# SecurityHost_v1_0.net
KiCad netlist of a schematic drawn in Altium Designer
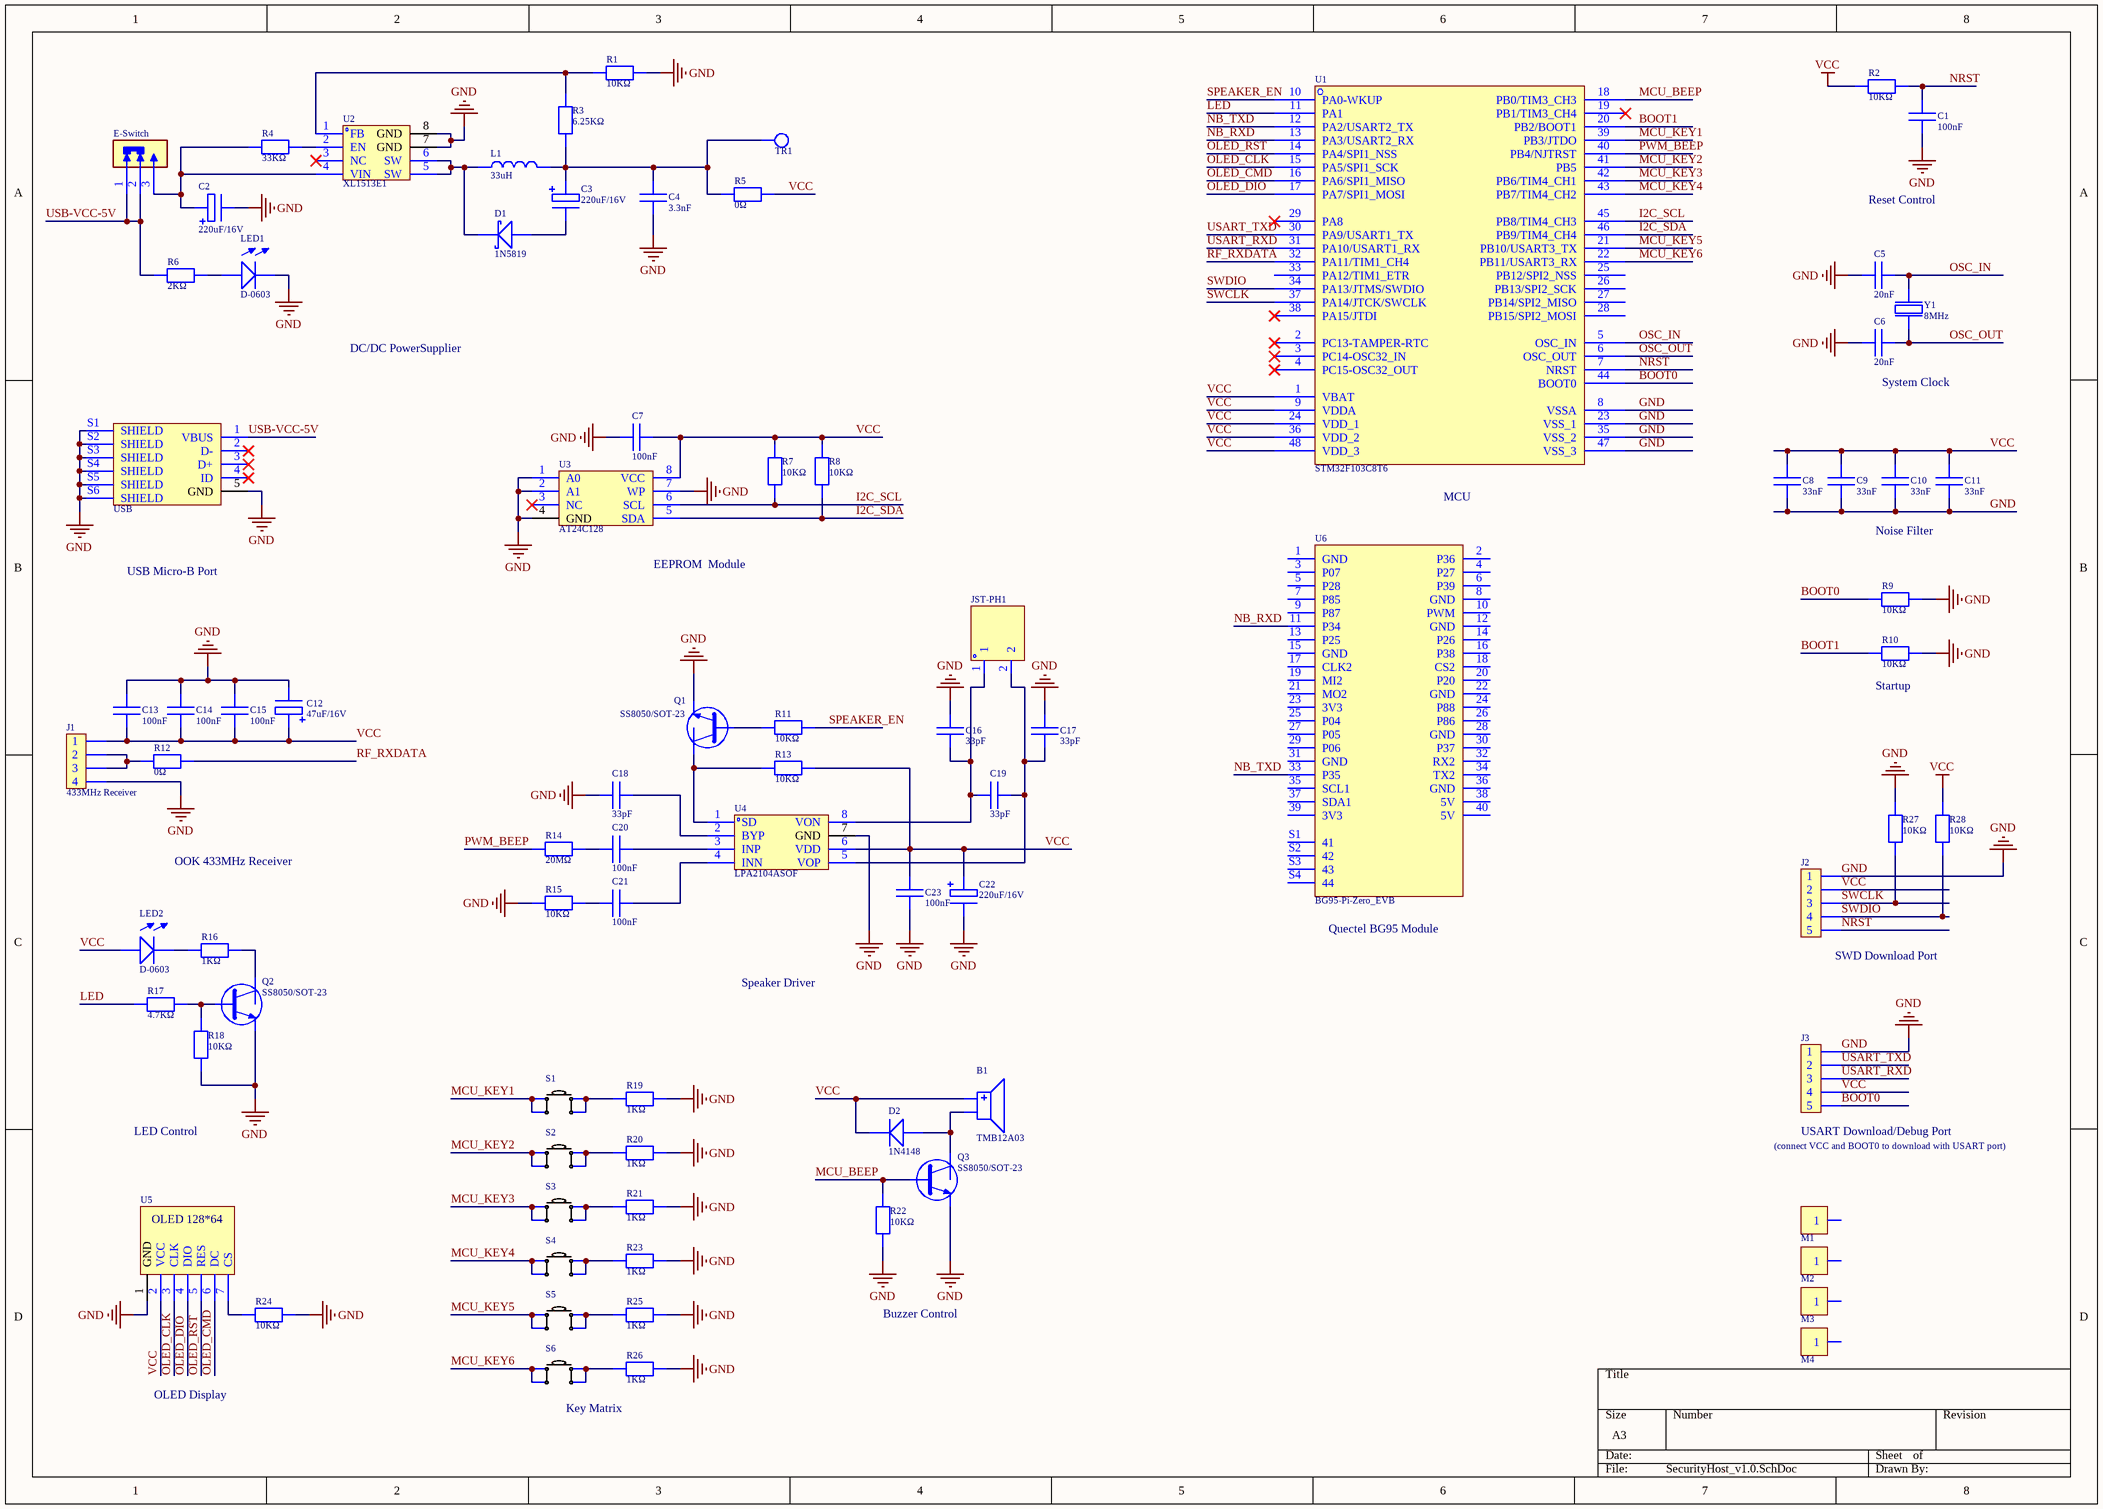
[diagram p0: SecurityHost_v1.0.SchDoc]

(export (version "E")
  (design (tool "Eeschema 10.0.6"))
  (components
    (comp (ref "B1")
      (value "TMB12A03")
      (footprint "Buzzer_TH_BD12.0")
      (libsource (lib "Schematic Library_General") (part "Buzzer_TMB12A03"))
    )
    (comp (ref "C1")
      (value "100nF")
      (footprint "C0603")
      (libsource (lib "Schematic Library_General") (part "Capacitor_0603"))
    )
    (comp (ref "C2")
      (value "220uF/16V")
      (footprint "C(Electrolytic)_SMD-D6.3mm_L7.7mm")
      (libsource (lib "Schematic Library_General") (part "Capacitor_Electrolytic-SMD"))
    )
    (comp (ref "C3")
      (value "220uF/16V")
      (footprint "C(Electrolytic)_SMD-D6.3mm_L7.7mm")
      (libsource (lib "Schematic Library_General") (part "Capacitor_Electrolytic-SMD"))
    )
    (comp (ref "C4")
      (value "3.3nF")
      (footprint "C0603")
      (libsource (lib "Schematic Library_General") (part "Capacitor_0603"))
    )
    (comp (ref "C5")
      (value "20nF")
      (footprint "C0603")
      (libsource (lib "Schematic Library_General") (part "Capacitor_0603"))
    )
    (comp (ref "C6")
      (value "20nF")
      (footprint "C0603")
      (libsource (lib "Schematic Library_General") (part "Capacitor_0603"))
    )
    (comp (ref "C7")
      (value "100nF")
      (footprint "C0603")
      (libsource (lib "Schematic Library_General") (part "Capacitor_0603"))
    )
    (comp (ref "C8")
      (value "33nF")
      (footprint "C0603")
      (libsource (lib "Schematic Library_General") (part "Capacitor_0603"))
    )
    (comp (ref "C9")
      (value "33nF")
      (footprint "C0603")
      (libsource (lib "Schematic Library_General") (part "Capacitor_0603"))
    )
    (comp (ref "C10")
      (value "33nF")
      (footprint "C0603")
      (libsource (lib "Schematic Library_General") (part "Capacitor_0603"))
    )
    (comp (ref "C11")
      (value "33nF")
      (footprint "C0603")
      (libsource (lib "Schematic Library_General") (part "Capacitor_0603"))
    )
    (comp (ref "C12")
      (value "47uF/16V")
      (footprint "C(Electrolytic)_SMD-D6.3mm_L7.7mm")
      (libsource (lib "Schematic Library_General") (part "Capacitor_Electrolytic-SMD"))
    )
    (comp (ref "C13")
      (value "100nF")
      (footprint "C0603")
      (libsource (lib "Schematic Library_General") (part "Capacitor_0603"))
    )
    (comp (ref "C14")
      (value "100nF")
      (footprint "C0603")
      (libsource (lib "Schematic Library_General") (part "Capacitor_0603"))
    )
    (comp (ref "C15")
      (value "100nF")
      (footprint "C0603")
      (libsource (lib "Schematic Library_General") (part "Capacitor_0603"))
    )
    (comp (ref "C16")
      (value "33pF")
      (footprint "C0603")
      (libsource (lib "Schematic Library_General") (part "Capacitor_0603"))
    )
    (comp (ref "C17")
      (value "33pF")
      (footprint "C0603")
      (libsource (lib "Schematic Library_General") (part "Capacitor_0603"))
    )
    (comp (ref "C18")
      (value "33pF")
      (footprint "C0603")
      (libsource (lib "Schematic Library_General") (part "Capacitor_0603"))
    )
    (comp (ref "C19")
      (value "33pF")
      (footprint "C0603")
      (libsource (lib "Schematic Library_General") (part "Capacitor_0603"))
    )
    (comp (ref "C20")
      (value "100nF")
      (footprint "C0603")
      (libsource (lib "Schematic Library_General") (part "Capacitor_0603"))
    )
    (comp (ref "C21")
      (value "100nF")
      (footprint "C0603")
      (libsource (lib "Schematic Library_General") (part "Capacitor_0603"))
    )
    (comp (ref "C22")
      (value "220uF/16V")
      (footprint "C(Electrolytic)_SMD-D6.3mm_L7.7mm")
      (libsource (lib "Schematic Library_General") (part "Capacitor_Electrolytic-SMD"))
    )
    (comp (ref "C23")
      (value "100nF")
      (footprint "C0603")
      (libsource (lib "Schematic Library_General") (part "Capacitor_0603"))
    )
    (comp (ref "D1")
      (value "1N5819")
      (footprint "SOD-123F")
      (libsource (lib "Schematic Library_General") (part "Schottky Diodes_SOD123F"))
    )
    (comp (ref "D2")
      (value "1N4148")
      (footprint "SOD-123")
      (libsource (lib "Schematic Library_General") (part "Diode-FastSwitching_SOD123"))
    )
    (comp (ref "E-Switch")
      (value "E-Switch_3Pin-Slide")
      (footprint "E-Switch_3Pin-Slide")
      (libsource (lib "Schematic Library_General") (part "E-Switch_3Pin-Slide"))
    )
    (comp (ref "J1")
      (value "433MHz Receiver")
      (footprint "PinSocket_4Pin-2.54mm")
      (description "Straight Single Row, Square Pitch, 2.54mm")
      (libsource (lib "Schematic Library_General") (part "PinSocket_4Pin"))
    )
    (comp (ref "J2")
      (value "SWD Download Port")
      (footprint "PinHeader_5Pin-2.54mm")
      (description "Straight Single Row, Square Pitch, 2.54mm")
      (libsource (lib "Schematic Library_General") (part "PinHeader_5Pin"))
    )
    (comp (ref "J3")
      (value "PinHeader_5Pin")
      (footprint "PinHeader_5Pin-2.54mm")
      (description "Straight Single Row, Square Pitch, 2.54mm")
      (libsource (lib "Schematic Library_General") (part "PinHeader_5Pin"))
    )
    (comp (ref "JST-PH1")
      (value "JST-PH2.0_2Pin-TH-Vertical")
      (footprint "Connector-JST-PH2.0-2Pin_TH-Vertical")
      (libsource (lib "Schematic Library_General") (part "JST-PH2.0_2Pin-TH-Vertical"))
    )
    (comp (ref "L1")
      (value "33uH")
      (footprint "L1040-Integrated Molded")
      (libsource (lib "Schematic Library_General") (part "Inductor_Integrated Molded_1040"))
    )
    (comp (ref "LED1")
      (value "D-0603")
      (footprint "LED0603-Castellated")
      (libsource (lib "Schematic Library_General") (part "LED_0603"))
    )
    (comp (ref "LED2")
      (value "D-0603")
      (footprint "LED0603-Castellated")
      (libsource (lib "Schematic Library_General") (part "LED_0603"))
    )
    (comp (ref "M1")
      (value "PCB Mounting Hole")
      (footprint "PCB Mounting Hole")
      (description "Mounting Hole")
      (libsource (lib "Schematic Library_General") (part "PCB Mounting Hole"))
    )
    (comp (ref "M2")
      (value "PCB Mounting Hole")
      (footprint "PCB Mounting Hole")
      (description "Mounting Hole")
      (libsource (lib "Schematic Library_General") (part "PCB Mounting Hole"))
    )
    (comp (ref "M3")
      (value "PCB Mounting Hole")
      (footprint "PCB Mounting Hole")
      (description "Mounting Hole")
      (libsource (lib "Schematic Library_General") (part "PCB Mounting Hole"))
    )
    (comp (ref "M4")
      (value "PCB Mounting Hole")
      (footprint "PCB Mounting Hole")
      (description "Mounting Hole")
      (libsource (lib "Schematic Library_General") (part "PCB Mounting Hole"))
    )
    (comp (ref "Q1")
      (value "SS8050/SOT-23")
      (footprint "SOT-23-3")
      (libsource (lib "") (part "NPN_SOT-23-3_1"))
    )
    (comp (ref "Q2")
      (value "SS8050/SOT-23")
      (footprint "SOT-23-3")
      (libsource (lib "Schematic Library_General") (part "NPN_SOT-23-3"))
    )
    (comp (ref "Q3")
      (value "SS8050/SOT-23")
      (footprint "SOT-23-3")
      (libsource (lib "Schematic Library_General") (part "NPN_SOT-23-3"))
    )
    (comp (ref "R1")
      (value "10KΩ")
      (footprint "R0805")
      (libsource (lib "Schematic Library_General") (part "Resistor_0805"))
    )
    (comp (ref "R2")
      (value "10KΩ")
      (footprint "R0603")
      (libsource (lib "Schematic Library_General") (part "Resistor_0603"))
    )
    (comp (ref "R3") (value "6.25KΩ") (footprint "R0805") (libsource (lib "") (part "Resistor_0805_1")))
    (comp (ref "R4")
      (value "33KΩ")
      (footprint "R0603")
      (libsource (lib "Schematic Library_General") (part "Resistor_0603"))
    )
    (comp (ref "R5")
      (value "0Ω")
      (footprint "R0805")
      (libsource (lib "Schematic Library_General") (part "Resistor_0805"))
    )
    (comp (ref "R6")
      (value "2KΩ")
      (footprint "R0805")
      (libsource (lib "Schematic Library_General") (part "Resistor_0805"))
    )
    (comp (ref "R7") (value "10KΩ") (footprint "R0603") (libsource (lib "") (part "Resistor_0603_2")))
    (comp (ref "R8") (value "10KΩ") (footprint "R0603") (libsource (lib "") (part "Resistor_0603_2")))
    (comp (ref "R9")
      (value "10KΩ")
      (footprint "R0603")
      (libsource (lib "Schematic Library_General") (part "Resistor_0603"))
    )
    (comp (ref "R10")
      (value "10KΩ")
      (footprint "R0603")
      (libsource (lib "Schematic Library_General") (part "Resistor_0603"))
    )
    (comp (ref "R11") (value "10KΩ") (footprint "R0603") (libsource (lib "") (part "Resistor_0603_1")))
    (comp (ref "R12")
      (value "0Ω")
      (footprint "R0805")
      (libsource (lib "Schematic Library_General") (part "Resistor_0805"))
    )
    (comp (ref "R13")
      (value "10KΩ")
      (footprint "R0603")
      (libsource (lib "Schematic Library_General") (part "Resistor_0603"))
    )
    (comp (ref "R14")
      (value "20MΩ")
      (footprint "R0603")
      (libsource (lib "Schematic Library_General") (part "Resistor_0603"))
    )
    (comp (ref "R15")
      (value "10KΩ")
      (footprint "R0603")
      (libsource (lib "Schematic Library_General") (part "Resistor_0603"))
    )
    (comp (ref "R16")
      (value "1KΩ")
      (footprint "R0603")
      (libsource (lib "Schematic Library_General") (part "Resistor_0603"))
    )
    (comp (ref "R17")
      (value "4.7KΩ")
      (footprint "R0603")
      (libsource (lib "Schematic Library_General") (part "Resistor_0603"))
    )
    (comp (ref "R18") (value "10KΩ") (footprint "R0603") (libsource (lib "") (part "Resistor_0603_2")))
    (comp (ref "R19")
      (value "1KΩ")
      (footprint "R0603")
      (libsource (lib "Schematic Library_General") (part "Resistor_0603"))
    )
    (comp (ref "R20")
      (value "1KΩ")
      (footprint "R0603")
      (libsource (lib "Schematic Library_General") (part "Resistor_0603"))
    )
    (comp (ref "R21")
      (value "1KΩ")
      (footprint "R0603")
      (libsource (lib "Schematic Library_General") (part "Resistor_0603"))
    )
    (comp (ref "R22") (value "10KΩ") (footprint "R0603") (libsource (lib "") (part "Resistor_0603_2")))
    (comp (ref "R23")
      (value "1KΩ")
      (footprint "R0603")
      (libsource (lib "Schematic Library_General") (part "Resistor_0603"))
    )
    (comp (ref "R24")
      (value "10KΩ")
      (footprint "R0603")
      (libsource (lib "Schematic Library_General") (part "Resistor_0603"))
    )
    (comp (ref "R25")
      (value "1KΩ")
      (footprint "R0603")
      (libsource (lib "Schematic Library_General") (part "Resistor_0603"))
    )
    (comp (ref "R26")
      (value "1KΩ")
      (footprint "R0603")
      (libsource (lib "Schematic Library_General") (part "Resistor_0603"))
    )
    (comp (ref "R27") (value "10KΩ") (footprint "R0603") (libsource (lib "") (part "Resistor_0603_2")))
    (comp (ref "R28") (value "10KΩ") (footprint "R0603") (libsource (lib "") (part "Resistor_0603_2")))
    (comp (ref "S1")
      (value "Button_Push_4Pin_TH")
      (footprint "Tactile Switch_TH_SPST-L6.0-W6.0")
      (libsource (lib "Schematic Library_General") (part "Button_Push_4Pin_TH"))
    )
    (comp (ref "S2")
      (value "Button_Push_4Pin_TH")
      (footprint "Tactile Switch_TH_SPST-L6.0-W6.0")
      (libsource (lib "Schematic Library_General") (part "Button_Push_4Pin_TH"))
    )
    (comp (ref "S3")
      (value "Button_Push_4Pin_TH")
      (footprint "Tactile Switch_TH_SPST-L6.0-W6.0")
      (libsource (lib "Schematic Library_General") (part "Button_Push_4Pin_TH"))
    )
    (comp (ref "S4")
      (value "Button_Push_4Pin_TH")
      (footprint "Tactile Switch_TH_SPST-L6.0-W6.0")
      (libsource (lib "Schematic Library_General") (part "Button_Push_4Pin_TH"))
    )
    (comp (ref "S5")
      (value "Button_Push_4Pin_TH")
      (footprint "Tactile Switch_TH_SPST-L6.0-W6.0")
      (libsource (lib "Schematic Library_General") (part "Button_Push_4Pin_TH"))
    )
    (comp (ref "S6")
      (value "Button_Push_4Pin_TH")
      (footprint "Tactile Switch_TH_SPST-L6.0-W6.0")
      (libsource (lib "Schematic Library_General") (part "Button_Push_4Pin_TH"))
    )
    (comp (ref "TR1")
      (value "Test Ring")
      (footprint "Test Ring_TH-BD2.54mm")
      (libsource (lib "Schematic Library_General") (part "Test Ring"))
    )
    (comp (ref "U1")
      (value "STM32F103C8T6")
      (footprint "LQFP_48Pin_L7.0-W7.0-P0.5")
      (libsource (lib "Schematic Library_General") (part "STM32_LQFP-48Pin-7x7mm"))
    )
    (comp (ref "U2")
      (value "XL1513E1")
      (footprint "SOIC_8Pin-L5.0-W4.0")
      (description "3.6V to 18V Input, 0.8V to 16V Output, Step-down type 2A")
      (libsource (lib "Schematic Library_General") (part "DC/DC Converter_XL1513_SOP8"))
    )
    (comp (ref "U3")
      (value "AT24C128")
      (footprint "SOIC_8Pin-L5.0-W4.0")
      (libsource (lib "Schematic Library_General") (part "EEPROM_AT24C128_SOP8"))
    )
    (comp (ref "U4")
      (value "LPA2104ASOF")
      (footprint "SOIC_8Pin-L5.0-W4.0")
      (libsource (lib "Schematic Library_General") (part "Audio Amplifier_SOP8"))
    )
    (comp (ref "U5")
      (value "OLED Display_7Pin")
      (footprint "OLED Display_7Pin")
      (description "0.96'', 128x64")
      (libsource (lib "Schematic Library_General") (part "OLED Display_7Pin"))
    )
    (comp (ref "U6")
      (value "BG95-Pi-Zero_EVB")
      (footprint "Quectel-BG95-Pi-Zero_EVB_PinSocket")
      (description "P34: USART4_RX, P35: USART4_TX")
      (libsource (lib "Schematic Library_General") (part "Quectel-BG95-Pi-Zero_EVB"))
    )
    (comp (ref "USB")
      (value "USB_Micro-B-Molex")
      (footprint "USB_Micro-B")
      (libsource (lib "Schematic Library_General") (part "USB_Micro-B-Molex"))
    )
    (comp (ref "Y1")
      (value "8MHz")
      (footprint "Crystal_TH_HC-49S-L11.5-W4.5")
      (libsource (lib "Schematic Library_General") (part "Crystal_2Pin_TH"))
    )
  )
  (nets
    (net (code "1") (name "/BOOT0") (class "Default")
      (node (ref "J3") (pin "5") (pinfunction "5_5") (pintype "passive"))
      (node (ref "R9") (pin "1") (pintype "passive"))
      (node (ref "U1") (pin "44") (pinfunction "BOOT0_44") (pintype "passive"))
    )
    (net (code "2") (name "/BOOT1") (class "Default")
      (node (ref "R10") (pin "1") (pintype "passive"))
      (node (ref "U1") (pin "20") (pinfunction "PB2/BOOT1_20") (pintype "passive"))
    )
    (net (code "3") (name "/I2C_SCL") (class "Default")
      (node (ref "R7") (pin "1") (pintype "passive"))
      (node (ref "U1") (pin "45") (pinfunction "PB8/TIM4_CH3_45") (pintype "passive"))
      (node (ref "U3") (pin "6") (pinfunction "SCL_6") (pintype "passive"))
    )
    (net (code "4") (name "/I2C_SDA") (class "Default")
      (node (ref "R8") (pin "1") (pintype "passive"))
      (node (ref "U1") (pin "46") (pinfunction "PB9/TIM4_CH4_46") (pintype "passive"))
      (node (ref "U3") (pin "5") (pinfunction "SDA_5") (pintype "passive"))
    )
    (net (code "5") (name "/LED") (class "Default")
      (node (ref "R17") (pin "1") (pintype "passive"))
      (node (ref "U1") (pin "11") (pinfunction "PA1_11") (pintype "passive"))
    )
    (net (code "6") (name "/MCU_BEEP") (class "Default")
      (node (ref "Q3") (pin "1") (pintype "passive"))
      (node (ref "R22") (pin "2") (pintype "passive"))
      (node (ref "U1") (pin "18") (pinfunction "PB0/TIM3_CH3_18") (pintype "passive"))
    )
    (net (code "7") (name "/MCU_KEY1") (class "Default")
      (node (ref "S1") (pin "1") (pinfunction "1_1") (pintype "passive"))
      (node (ref "S1") (pin "2") (pinfunction "2_2") (pintype "passive"))
      (node (ref "U1") (pin "39") (pinfunction "PB3/JTDO_39") (pintype "passive"))
    )
    (net (code "8") (name "/MCU_KEY2") (class "Default")
      (node (ref "S2") (pin "1") (pinfunction "1_1") (pintype "passive"))
      (node (ref "S2") (pin "2") (pinfunction "2_2") (pintype "passive"))
      (node (ref "U1") (pin "41") (pinfunction "PB5_41") (pintype "passive"))
    )
    (net (code "9") (name "/MCU_KEY3") (class "Default")
      (node (ref "S3") (pin "1") (pinfunction "1_1") (pintype "passive"))
      (node (ref "S3") (pin "2") (pinfunction "2_2") (pintype "passive"))
      (node (ref "U1") (pin "42") (pinfunction "PB6/TIM4_CH1_42") (pintype "passive"))
    )
    (net (code "10") (name "/MCU_KEY4") (class "Default")
      (node (ref "S4") (pin "1") (pinfunction "1_1") (pintype "passive"))
      (node (ref "S4") (pin "2") (pinfunction "2_2") (pintype "passive"))
      (node (ref "U1") (pin "43") (pinfunction "PB7/TIM4_CH2_43") (pintype "passive"))
    )
    (net (code "11") (name "/MCU_KEY5") (class "Default")
      (node (ref "S5") (pin "1") (pinfunction "1_1") (pintype "passive"))
      (node (ref "S5") (pin "2") (pinfunction "2_2") (pintype "passive"))
      (node (ref "U1") (pin "21") (pinfunction "PB10/USART3_TX_21") (pintype "passive"))
    )
    (net (code "12") (name "/MCU_KEY6") (class "Default")
      (node (ref "S6") (pin "1") (pinfunction "1_1") (pintype "passive"))
      (node (ref "S6") (pin "2") (pinfunction "2_2") (pintype "passive"))
      (node (ref "U1") (pin "22") (pinfunction "PB11/USART3_RX_22") (pintype "passive"))
    )
    (net (code "13") (name "/NB_RXD") (class "Default")
      (node (ref "U1") (pin "13") (pinfunction "PA3/USART2_RX_13") (pintype "passive"))
      (node (ref "U6") (pin "11") (pinfunction "P34_11") (pintype "passive"))
    )
    (net (code "14") (name "/NB_TXD") (class "Default")
      (node (ref "U1") (pin "12") (pinfunction "PA2/USART2_TX_12") (pintype "passive"))
      (node (ref "U6") (pin "33") (pinfunction "P35_33") (pintype "passive"))
    )
    (net (code "15") (name "/NRST") (class "Default")
      (node (ref "C1") (pin "2") (pintype "passive"))
      (node (ref "J2") (pin "5") (pinfunction "5_5") (pintype "passive"))
      (node (ref "R2") (pin "2") (pintype "passive"))
      (node (ref "U1") (pin "7") (pinfunction "NRST_7") (pintype "passive"))
    )
    (net (code "16") (name "/OLED_CLK") (class "Default")
      (node (ref "U1") (pin "15") (pinfunction "PA5/SPI1_SCK_15") (pintype "passive"))
      (node (ref "U5") (pin "3") (pinfunction "CLK_3") (pintype "passive"))
    )
    (net (code "17") (name "/OLED_CMD") (class "Default")
      (node (ref "U1") (pin "16") (pinfunction "PA6/SPI1_MISO_16") (pintype "passive"))
      (node (ref "U5") (pin "6") (pinfunction "DC_6") (pintype "passive"))
    )
    (net (code "18") (name "/OLED_DIO") (class "Default")
      (node (ref "U1") (pin "17") (pinfunction "PA7/SPI1_MOSI_17") (pintype "passive"))
      (node (ref "U5") (pin "4") (pinfunction "DIO_4") (pintype "passive"))
    )
    (net (code "19") (name "/OLED_RST") (class "Default")
      (node (ref "U1") (pin "14") (pinfunction "PA4/SPI1_NSS_14") (pintype "passive"))
      (node (ref "U5") (pin "5") (pinfunction "RES_5") (pintype "passive"))
    )
    (net (code "20") (name "/OSC_IN") (class "Default")
      (node (ref "C5") (pin "2") (pintype "passive"))
      (node (ref "U1") (pin "5") (pinfunction "OSC_IN_5") (pintype "passive"))
      (node (ref "Y1") (pin "2") (pinfunction "2_2") (pintype "passive"))
    )
    (net (code "21") (name "/OSC_OUT") (class "Default")
      (node (ref "C6") (pin "2") (pintype "passive"))
      (node (ref "U1") (pin "6") (pinfunction "OSC_OUT_6") (pintype "passive"))
      (node (ref "Y1") (pin "1") (pinfunction "1_1") (pintype "passive"))
    )
    (net (code "22") (name "/PWM_BEEP") (class "Default")
      (node (ref "R14") (pin "1") (pintype "passive"))
      (node (ref "U1") (pin "40") (pinfunction "PB4/NJTRST_40") (pintype "passive"))
    )
    (net (code "23") (name "/RF_RXDATA") (class "Default")
      (node (ref "R12") (pin "2") (pintype "passive"))
      (node (ref "U1") (pin "32") (pinfunction "PA11/TIM1_CH4_32") (pintype "passive"))
    )
    (net (code "24") (name "/SPEAKER_EN") (class "Default")
      (node (ref "R11") (pin "1") (pintype "passive"))
      (node (ref "U1") (pin "10") (pinfunction "PA0-WKUP_10") (pintype "passive"))
    )
    (net (code "25") (name "/SWCLK") (class "Default")
      (node (ref "J2") (pin "3") (pinfunction "3_3") (pintype "passive"))
      (node (ref "R27") (pin "1") (pintype "passive"))
      (node (ref "U1") (pin "37") (pinfunction "PA14/JTCK/SWCLK_37") (pintype "passive"))
    )
    (net (code "26") (name "/SWDIO") (class "Default")
      (node (ref "J2") (pin "4") (pinfunction "4_4") (pintype "passive"))
      (node (ref "R28") (pin "1") (pintype "passive"))
      (node (ref "U1") (pin "34") (pinfunction "PA13/JTMS/SWDIO_34") (pintype "passive"))
    )
    (net (code "27") (name "/USART_RXD") (class "Default")
      (node (ref "J3") (pin "3") (pinfunction "3_3") (pintype "passive"))
      (node (ref "U1") (pin "31") (pinfunction "PA10/USART1_RX_31") (pintype "passive"))
    )
    (net (code "28") (name "/USART_TXD") (class "Default")
      (node (ref "J3") (pin "2") (pinfunction "2_2") (pintype "passive"))
      (node (ref "U1") (pin "30") (pinfunction "PA9/USART1_TX_30") (pintype "passive"))
    )
    (net (code "29") (name "/USB-VCC-5V") (class "Default")
      (node (ref "E-Switch") (pin "1") (pinfunction "NC_1") (pintype "passive"))
      (node (ref "E-Switch") (pin "2") (pinfunction "COM_2") (pintype "passive"))
      (node (ref "R6") (pin "1") (pintype "passive"))
      (node (ref "USB") (pin "1") (pinfunction "VBUS_1") (pintype "passive"))
    )
    (net (code "30") (name "GND") (class "Default")
      (node (ref "C1") (pin "1") (pintype "passive"))
      (node (ref "C10") (pin "1") (pintype "passive"))
      (node (ref "C11") (pin "1") (pintype "passive"))
      (node (ref "C12") (pin "2") (pintype "passive"))
      (node (ref "C13") (pin "2") (pintype "passive"))
      (node (ref "C14") (pin "2") (pintype "passive"))
      (node (ref "C15") (pin "2") (pintype "passive"))
      (node (ref "C16") (pin "2") (pintype "passive"))
      (node (ref "C17") (pin "2") (pintype "passive"))
      (node (ref "C18") (pin "2") (pintype "passive"))
      (node (ref "C2") (pin "2") (pintype "passive"))
      (node (ref "C22") (pin "2") (pintype "passive"))
      (node (ref "C23") (pin "2") (pintype "passive"))
      (node (ref "C4") (pin "1") (pintype "passive"))
      (node (ref "C5") (pin "1") (pintype "passive"))
      (node (ref "C6") (pin "1") (pintype "passive"))
      (node (ref "C7") (pin "1") (pintype "passive"))
      (node (ref "C8") (pin "1") (pintype "passive"))
      (node (ref "C9") (pin "1") (pintype "passive"))
      (node (ref "J1") (pin "4") (pinfunction "4_4") (pintype "passive"))
      (node (ref "J2") (pin "1") (pinfunction "1_1") (pintype "passive"))
      (node (ref "J3") (pin "1") (pinfunction "1_1") (pintype "passive"))
      (node (ref "LED1") (pin "2") (pintype "passive"))
      (node (ref "Q1") (pin "2") (pintype "passive"))
      (node (ref "Q2") (pin "2") (pintype "passive"))
      (node (ref "Q3") (pin "2") (pintype "passive"))
      (node (ref "R1") (pin "2") (pintype "passive"))
      (node (ref "R10") (pin "2") (pintype "passive"))
      (node (ref "R15") (pin "1") (pintype "passive"))
      (node (ref "R18") (pin "1") (pintype "passive"))
      (node (ref "R19") (pin "2") (pintype "passive"))
      (node (ref "R20") (pin "2") (pintype "passive"))
      (node (ref "R21") (pin "2") (pintype "passive"))
      (node (ref "R22") (pin "1") (pintype "passive"))
      (node (ref "R23") (pin "2") (pintype "passive"))
      (node (ref "R24") (pin "2") (pintype "passive"))
      (node (ref "R25") (pin "2") (pintype "passive"))
      (node (ref "R26") (pin "2") (pintype "passive"))
      (node (ref "R27") (pin "2") (pintype "passive"))
      (node (ref "R9") (pin "2") (pintype "passive"))
      (node (ref "U1") (pin "23") (pinfunction "VSS_1_23") (pintype "passive"))
      (node (ref "U1") (pin "35") (pinfunction "VSS_2_35") (pintype "passive"))
      (node (ref "U1") (pin "47") (pinfunction "VSS_3_47") (pintype "passive"))
      (node (ref "U1") (pin "8") (pinfunction "VSSA_8") (pintype "passive"))
      (node (ref "U2") (pin "7") (pinfunction "GND_7") (pintype "passive"))
      (node (ref "U2") (pin "8") (pinfunction "GND_8") (pintype "passive"))
      (node (ref "U3") (pin "1") (pinfunction "A0_1") (pintype "passive"))
      (node (ref "U3") (pin "2") (pinfunction "A1_2") (pintype "passive"))
      (node (ref "U3") (pin "4") (pinfunction "GND_4") (pintype "passive"))
      (node (ref "U3") (pin "7") (pinfunction "WP_7") (pintype "passive"))
      (node (ref "U4") (pin "7") (pinfunction "GND_7") (pintype "passive"))
      (node (ref "U5") (pin "1") (pinfunction "GND_1") (pintype "passive"))
      (node (ref "USB") (pin "5") (pinfunction "GND_5") (pintype "passive"))
      (node (ref "USB") (pin "S1") (pinfunction "SHIELD_S1") (pintype "passive"))
      (node (ref "USB") (pin "S2") (pinfunction "SHIELD_S2") (pintype "passive"))
      (node (ref "USB") (pin "S3") (pinfunction "SHIELD_S3") (pintype "passive"))
      (node (ref "USB") (pin "S4") (pinfunction "SHIELD_S4") (pintype "passive"))
      (node (ref "USB") (pin "S5") (pinfunction "SHIELD_S5") (pintype "passive"))
      (node (ref "USB") (pin "S6") (pinfunction "SHIELD_S6") (pintype "passive"))
    )
    (net (code "31") (name "Net-(B1-Pad2)") (class "Default")
      (node (ref "B1") (pin "2") (pintype "passive"))
      (node (ref "D2") (pin "2") (pintype "passive"))
      (node (ref "Q3") (pin "3") (pintype "passive"))
    )
    (net (code "32") (name "Net-(C3-Pad1)") (class "Default")
      (node (ref "C3") (pin "1") (pintype "passive"))
      (node (ref "C4") (pin "2") (pintype "passive"))
      (node (ref "L1") (pin "2") (pintype "passive"))
      (node (ref "R3") (pin "1") (pintype "passive"))
      (node (ref "R5") (pin "1") (pintype "passive"))
      (node (ref "TR1") (pin "1") (pinfunction "1_1") (pintype "passive"))
    )
    (net (code "33") (name "Net-(C3-Pad2)") (class "Default")
      (node (ref "C3") (pin "2") (pintype "passive"))
      (node (ref "D1") (pin "2") (pintype "passive"))
    )
    (net (code "34") (name "Net-(C20-Pad1)") (class "Default")
      (node (ref "C20") (pin "1") (pintype "passive"))
      (node (ref "R14") (pin "2") (pintype "passive"))
    )
    (net (code "35") (name "Net-(C21-Pad1)") (class "Default")
      (node (ref "C21") (pin "1") (pintype "passive"))
      (node (ref "R15") (pin "2") (pintype "passive"))
    )
    (net (code "36") (name "Net-(D1-Pad1)") (class "Default")
      (node (ref "D1") (pin "1") (pintype "passive"))
      (node (ref "L1") (pin "1") (pintype "passive"))
      (node (ref "U2") (pin "5") (pinfunction "SW_5") (pintype "passive"))
      (node (ref "U2") (pin "6") (pinfunction "SW_6") (pintype "passive"))
    )
    (net (code "37") (name "Net-(E-Switch-NO)") (class "Default")
      (node (ref "C2") (pin "1") (pintype "passive"))
      (node (ref "E-Switch") (pin "3") (pinfunction "NO_3") (pintype "passive"))
      (node (ref "R4") (pin "1") (pintype "passive"))
      (node (ref "U2") (pin "4") (pinfunction "VIN_4") (pintype "passive"))
    )
    (net (code "38") (name "Net-(J1-Pad2)") (class "Default")
      (node (ref "J1") (pin "2") (pinfunction "2_2") (pintype "passive"))
      (node (ref "J1") (pin "3") (pinfunction "3_3") (pintype "passive"))
      (node (ref "R12") (pin "1") (pintype "passive"))
    )
    (net (code "39") (name "Net-(LED1-Pad1)") (class "Default")
      (node (ref "LED1") (pin "1") (pintype "passive"))
      (node (ref "R6") (pin "2") (pintype "passive"))
    )
    (net (code "40") (name "Net-(LED2-Pad2)") (class "Default")
      (node (ref "LED2") (pin "2") (pintype "passive"))
      (node (ref "R16") (pin "1") (pintype "passive"))
    )
    (net (code "41") (name "Net-(Q1-Pad1)") (class "Default")
      (node (ref "Q1") (pin "1") (pintype "passive"))
      (node (ref "R11") (pin "2") (pintype "passive"))
    )
    (net (code "42") (name "Net-(Q2-Pad1)") (class "Default")
      (node (ref "Q2") (pin "1") (pintype "passive"))
      (node (ref "R17") (pin "2") (pintype "passive"))
      (node (ref "R18") (pin "2") (pintype "passive"))
    )
    (net (code "43") (name "Net-(Q2-Pad3)") (class "Default")
      (node (ref "Q2") (pin "3") (pintype "passive"))
      (node (ref "R16") (pin "2") (pintype "passive"))
    )
    (net (code "44") (name "Net-(R19-Pad1)") (class "Default")
      (node (ref "R19") (pin "1") (pintype "passive"))
      (node (ref "S1") (pin "3") (pinfunction "3_3") (pintype "passive"))
      (node (ref "S1") (pin "4") (pinfunction "4_4") (pintype "passive"))
    )
    (net (code "45") (name "Net-(R20-Pad1)") (class "Default")
      (node (ref "R20") (pin "1") (pintype "passive"))
      (node (ref "S2") (pin "3") (pinfunction "3_3") (pintype "passive"))
      (node (ref "S2") (pin "4") (pinfunction "4_4") (pintype "passive"))
    )
    (net (code "46") (name "Net-(R21-Pad1)") (class "Default")
      (node (ref "R21") (pin "1") (pintype "passive"))
      (node (ref "S3") (pin "3") (pinfunction "3_3") (pintype "passive"))
      (node (ref "S3") (pin "4") (pinfunction "4_4") (pintype "passive"))
    )
    (net (code "47") (name "Net-(R23-Pad1)") (class "Default")
      (node (ref "R23") (pin "1") (pintype "passive"))
      (node (ref "S4") (pin "3") (pinfunction "3_3") (pintype "passive"))
      (node (ref "S4") (pin "4") (pinfunction "4_4") (pintype "passive"))
    )
    (net (code "48") (name "Net-(R25-Pad1)") (class "Default")
      (node (ref "R25") (pin "1") (pintype "passive"))
      (node (ref "S5") (pin "3") (pinfunction "3_3") (pintype "passive"))
      (node (ref "S5") (pin "4") (pinfunction "4_4") (pintype "passive"))
    )
    (net (code "49") (name "Net-(R26-Pad1)") (class "Default")
      (node (ref "R26") (pin "1") (pintype "passive"))
      (node (ref "S6") (pin "3") (pinfunction "3_3") (pintype "passive"))
      (node (ref "S6") (pin "4") (pinfunction "4_4") (pintype "passive"))
    )
    (net (code "50") (name "Net-(U2-EN)") (class "Default")
      (node (ref "R4") (pin "2") (pintype "passive"))
      (node (ref "U2") (pin "2") (pinfunction "EN_2") (pintype "passive"))
    )
    (net (code "51") (name "Net-(U2-FB)") (class "Default")
      (node (ref "R1") (pin "1") (pintype "passive"))
      (node (ref "R3") (pin "2") (pintype "passive"))
      (node (ref "U2") (pin "1") (pinfunction "FB_1") (pintype "passive"))
    )
    (net (code "52") (name "Net-(U4-BYP)") (class "Default")
      (node (ref "C18") (pin "1") (pintype "passive"))
      (node (ref "U4") (pin "2") (pinfunction "BYP_2") (pintype "passive"))
    )
    (net (code "53") (name "Net-(U4-INN)") (class "Default")
      (node (ref "C21") (pin "2") (pintype "passive"))
      (node (ref "U4") (pin "4") (pinfunction "INN_4") (pintype "passive"))
    )
    (net (code "54") (name "Net-(U4-INP)") (class "Default")
      (node (ref "C20") (pin "2") (pintype "passive"))
      (node (ref "U4") (pin "3") (pinfunction "INP_3") (pintype "passive"))
    )
    (net (code "55") (name "Net-(U4-SD)") (class "Default")
      (node (ref "Q1") (pin "3") (pintype "passive"))
      (node (ref "R13") (pin "1") (pintype "passive"))
      (node (ref "U4") (pin "1") (pinfunction "SD_1") (pintype "passive"))
    )
    (net (code "56") (name "Net-(U4-VON)") (class "Default")
      (node (ref "C16") (pin "1") (pintype "passive"))
      (node (ref "C19") (pin "1") (pintype "passive"))
      (node (ref "JST-PH1") (pin "1") (pinfunction "1_1") (pintype "passive"))
      (node (ref "U4") (pin "8") (pinfunction "VON_8") (pintype "passive"))
    )
    (net (code "57") (name "Net-(U4-VOP)") (class "Default")
      (node (ref "C17") (pin "1") (pintype "passive"))
      (node (ref "C19") (pin "2") (pintype "passive"))
      (node (ref "JST-PH1") (pin "2") (pinfunction "2_2") (pintype "passive"))
      (node (ref "U4") (pin "5") (pinfunction "VOP_5") (pintype "passive"))
    )
    (net (code "58") (name "Net-(U5-CS)") (class "Default")
      (node (ref "R24") (pin "1") (pintype "passive"))
      (node (ref "U5") (pin "7") (pinfunction "CS_7") (pintype "passive"))
    )
    (net (code "59") (name "VCC") (class "Default")
      (node (ref "B1") (pin "1") (pintype "passive"))
      (node (ref "C10") (pin "2") (pintype "passive"))
      (node (ref "C11") (pin "2") (pintype "passive"))
      (node (ref "C12") (pin "1") (pintype "passive"))
      (node (ref "C13") (pin "1") (pintype "passive"))
      (node (ref "C14") (pin "1") (pintype "passive"))
      (node (ref "C15") (pin "1") (pintype "passive"))
      (node (ref "C22") (pin "1") (pintype "passive"))
      (node (ref "C23") (pin "1") (pintype "passive"))
      (node (ref "C7") (pin "2") (pintype "passive"))
      (node (ref "C8") (pin "2") (pintype "passive"))
      (node (ref "C9") (pin "2") (pintype "passive"))
      (node (ref "D2") (pin "1") (pintype "passive"))
      (node (ref "J1") (pin "1") (pinfunction "1_1") (pintype "passive"))
      (node (ref "J2") (pin "2") (pinfunction "2_2") (pintype "passive"))
      (node (ref "J3") (pin "4") (pinfunction "4_4") (pintype "passive"))
      (node (ref "LED2") (pin "1") (pintype "passive"))
      (node (ref "R13") (pin "2") (pintype "passive"))
      (node (ref "R2") (pin "1") (pintype "passive"))
      (node (ref "R28") (pin "2") (pintype "passive"))
      (node (ref "R5") (pin "2") (pintype "passive"))
      (node (ref "R7") (pin "2") (pintype "passive"))
      (node (ref "R8") (pin "2") (pintype "passive"))
      (node (ref "U1") (pin "1") (pinfunction "VBAT_1") (pintype "passive"))
      (node (ref "U1") (pin "24") (pinfunction "VDD_1_24") (pintype "passive"))
      (node (ref "U1") (pin "36") (pinfunction "VDD_2_36") (pintype "passive"))
      (node (ref "U1") (pin "48") (pinfunction "VDD_3_48") (pintype "passive"))
      (node (ref "U1") (pin "9") (pinfunction "VDDA_9") (pintype "passive"))
      (node (ref "U3") (pin "8") (pinfunction "VCC_8") (pintype "passive"))
      (node (ref "U4") (pin "6") (pinfunction "VDD_6") (pintype "passive"))
      (node (ref "U5") (pin "2") (pinfunction "VCC_2") (pintype "passive"))
    )
    (net (code "60") (name "unconnected-(M1-Pad1)") (class "Default")
      (node (ref "M1") (pin "1") (pinfunction "1_1") (pintype "passive"))
    )
    (net (code "61") (name "unconnected-(M2-Pad1)") (class "Default")
      (node (ref "M2") (pin "1") (pinfunction "1_1") (pintype "passive"))
    )
    (net (code "62") (name "unconnected-(M3-Pad1)") (class "Default")
      (node (ref "M3") (pin "1") (pinfunction "1_1") (pintype "passive"))
    )
    (net (code "63") (name "unconnected-(M4-Pad1)") (class "Default")
      (node (ref "M4") (pin "1") (pinfunction "1_1") (pintype "passive"))
    )
    (net (code "64") (name "unconnected-(U1-PA8-Pad29)") (class "Default")
      (node (ref "U1") (pin "29") (pinfunction "PA8_29") (pintype "passive+no_connect"))
    )
    (net (code "65") (name "unconnected-(U1-PA12{slash}TIM1_ETR-Pad33)") (class "Default")
      (node (ref "U1") (pin "33") (pinfunction "PA12/TIM1_ETR_33") (pintype "passive"))
    )
    (net (code "66") (name "unconnected-(U1-PA15{slash}JTDI-Pad38)") (class "Default")
      (node (ref "U1") (pin "38") (pinfunction "PA15/JTDI_38") (pintype "passive+no_connect"))
    )
    (net (code "67") (name "unconnected-(U1-PB1{slash}TIM3_CH4-Pad19)") (class "Default")
      (node (ref "U1") (pin "19") (pinfunction "PB1/TIM3_CH4_19") (pintype "passive+no_connect"))
    )
    (net (code "68") (name "unconnected-(U1-PB12{slash}SPI2_NSS-Pad25)") (class "Default")
      (node (ref "U1") (pin "25") (pinfunction "PB12/SPI2_NSS_25") (pintype "passive"))
    )
    (net (code "69") (name "unconnected-(U1-PB13{slash}SPI2_SCK-Pad26)") (class "Default")
      (node (ref "U1") (pin "26") (pinfunction "PB13/SPI2_SCK_26") (pintype "passive"))
    )
    (net (code "70") (name "unconnected-(U1-PB14{slash}SPI2_MISO-Pad27)") (class "Default")
      (node (ref "U1") (pin "27") (pinfunction "PB14/SPI2_MISO_27") (pintype "passive"))
    )
    (net (code "71") (name "unconnected-(U1-PB15{slash}SPI2_MOSI-Pad28)") (class "Default")
      (node (ref "U1") (pin "28") (pinfunction "PB15/SPI2_MOSI_28") (pintype "passive"))
    )
    (net (code "72") (name "unconnected-(U1-PC13-TAMPER-RTC-Pad2)") (class "Default")
      (node (ref "U1") (pin "2") (pinfunction "PC13-TAMPER-RTC_2") (pintype "passive+no_connect"))
    )
    (net (code "73") (name "unconnected-(U1-PC14-OSC32_IN-Pad3)") (class "Default")
      (node (ref "U1") (pin "3") (pinfunction "PC14-OSC32_IN_3") (pintype "passive+no_connect"))
    )
    (net (code "74") (name "unconnected-(U1-PC15-OSC32_OUT-Pad4)") (class "Default")
      (node (ref "U1") (pin "4") (pinfunction "PC15-OSC32_OUT_4") (pintype "passive+no_connect"))
    )
    (net (code "75") (name "unconnected-(U2-NC-Pad3)") (class "Default")
      (node (ref "U2") (pin "3") (pinfunction "NC_3") (pintype "passive+no_connect"))
    )
    (net (code "76") (name "unconnected-(U3-NC-Pad3)") (class "Default")
      (node (ref "U3") (pin "3") (pinfunction "NC_3") (pintype "passive+no_connect"))
    )
    (net (code "77") (name "unconnected-(U6-3V3-Pad23)") (class "Default")
      (node (ref "U6") (pin "23") (pinfunction "3V3_23") (pintype "passive"))
    )
    (net (code "78") (name "unconnected-(U6-3V3-Pad39)") (class "Default")
      (node (ref "U6") (pin "39") (pinfunction "3V3_39") (pintype "passive"))
    )
    (net (code "79") (name "unconnected-(U6-5V-Pad38)") (class "Default")
      (node (ref "U6") (pin "38") (pinfunction "5V_38") (pintype "passive"))
    )
    (net (code "80") (name "unconnected-(U6-5V-Pad40)") (class "Default")
      (node (ref "U6") (pin "40") (pinfunction "5V_40") (pintype "passive"))
    )
    (net (code "81") (name "unconnected-(U6-41-PadS1)") (class "Default")
      (node (ref "U6") (pin "S1") (pinfunction "41_S1") (pintype "passive"))
    )
    (net (code "82") (name "unconnected-(U6-42-PadS2)") (class "Default")
      (node (ref "U6") (pin "S2") (pinfunction "42_S2") (pintype "passive"))
    )
    (net (code "83") (name "unconnected-(U6-43-PadS3)") (class "Default")
      (node (ref "U6") (pin "S3") (pinfunction "43_S3") (pintype "passive"))
    )
    (net (code "84") (name "unconnected-(U6-44-PadS4)") (class "Default")
      (node (ref "U6") (pin "S4") (pinfunction "44_S4") (pintype "passive"))
    )
    (net (code "85") (name "unconnected-(U6-CLK2-Pad17)") (class "Default")
      (node (ref "U6") (pin "17") (pinfunction "CLK2_17") (pintype "passive"))
    )
    (net (code "86") (name "unconnected-(U6-CS2-Pad18)") (class "Default")
      (node (ref "U6") (pin "18") (pinfunction "CS2_18") (pintype "passive"))
    )
    (net (code "87") (name "unconnected-(U6-GND-Pad1)") (class "Default")
      (node (ref "U6") (pin "1") (pinfunction "GND_1") (pintype "passive"))
    )
    (net (code "88") (name "unconnected-(U6-GND-Pad8)") (class "Default")
      (node (ref "U6") (pin "8") (pinfunction "GND_8") (pintype "passive"))
    )
    (net (code "89") (name "unconnected-(U6-GND-Pad12)") (class "Default")
      (node (ref "U6") (pin "12") (pinfunction "GND_12") (pintype "passive"))
    )
    (net (code "90") (name "unconnected-(U6-GND-Pad15)") (class "Default")
      (node (ref "U6") (pin "15") (pinfunction "GND_15") (pintype "passive"))
    )
    (net (code "91") (name "unconnected-(U6-GND-Pad22)") (class "Default")
      (node (ref "U6") (pin "22") (pinfunction "GND_22") (pintype "passive"))
    )
    (net (code "92") (name "unconnected-(U6-GND-Pad28)") (class "Default")
      (node (ref "U6") (pin "28") (pinfunction "GND_28") (pintype "passive"))
    )
    (net (code "93") (name "unconnected-(U6-GND-Pad31)") (class "Default")
      (node (ref "U6") (pin "31") (pinfunction "GND_31") (pintype "passive"))
    )
    (net (code "94") (name "unconnected-(U6-GND-Pad36)") (class "Default")
      (node (ref "U6") (pin "36") (pinfunction "GND_36") (pintype "passive"))
    )
    (net (code "95") (name "unconnected-(U6-MI2-Pad19)") (class "Default")
      (node (ref "U6") (pin "19") (pinfunction "MI2_19") (pintype "passive"))
    )
    (net (code "96") (name "unconnected-(U6-MO2-Pad21)") (class "Default")
      (node (ref "U6") (pin "21") (pinfunction "MO2_21") (pintype "passive"))
    )
    (net (code "97") (name "unconnected-(U6-P04-Pad25)") (class "Default")
      (node (ref "U6") (pin "25") (pinfunction "P04_25") (pintype "passive"))
    )
    (net (code "98") (name "unconnected-(U6-P05-Pad27)") (class "Default")
      (node (ref "U6") (pin "27") (pinfunction "P05_27") (pintype "passive"))
    )
    (net (code "99") (name "unconnected-(U6-P06-Pad29)") (class "Default")
      (node (ref "U6") (pin "29") (pinfunction "P06_29") (pintype "passive"))
    )
    (net (code "100") (name "unconnected-(U6-P07-Pad3)") (class "Default")
      (node (ref "U6") (pin "3") (pinfunction "P07_3") (pintype "passive"))
    )
    (net (code "101") (name "unconnected-(U6-P20-Pad20)") (class "Default")
      (node (ref "U6") (pin "20") (pinfunction "P20_20") (pintype "passive"))
    )
    (net (code "102") (name "unconnected-(U6-P25-Pad13)") (class "Default")
      (node (ref "U6") (pin "13") (pinfunction "P25_13") (pintype "passive"))
    )
    (net (code "103") (name "unconnected-(U6-P26-Pad14)") (class "Default")
      (node (ref "U6") (pin "14") (pinfunction "P26_14") (pintype "passive"))
    )
    (net (code "104") (name "unconnected-(U6-P27-Pad4)") (class "Default")
      (node (ref "U6") (pin "4") (pinfunction "P27_4") (pintype "passive"))
    )
    (net (code "105") (name "unconnected-(U6-P28-Pad5)") (class "Default")
      (node (ref "U6") (pin "5") (pinfunction "P28_5") (pintype "passive"))
    )
    (net (code "106") (name "unconnected-(U6-P36-Pad2)") (class "Default")
      (node (ref "U6") (pin "2") (pinfunction "P36_2") (pintype "passive"))
    )
    (net (code "107") (name "unconnected-(U6-P37-Pad30)") (class "Default")
      (node (ref "U6") (pin "30") (pinfunction "P37_30") (pintype "passive"))
    )
    (net (code "108") (name "unconnected-(U6-P38-Pad16)") (class "Default")
      (node (ref "U6") (pin "16") (pinfunction "P38_16") (pintype "passive"))
    )
    (net (code "109") (name "unconnected-(U6-P39-Pad6)") (class "Default")
      (node (ref "U6") (pin "6") (pinfunction "P39_6") (pintype "passive"))
    )
    (net (code "110") (name "unconnected-(U6-P85-Pad7)") (class "Default")
      (node (ref "U6") (pin "7") (pinfunction "P85_7") (pintype "passive"))
    )
    (net (code "111") (name "unconnected-(U6-P86-Pad26)") (class "Default")
      (node (ref "U6") (pin "26") (pinfunction "P86_26") (pintype "passive"))
    )
    (net (code "112") (name "unconnected-(U6-P87-Pad9)") (class "Default")
      (node (ref "U6") (pin "9") (pinfunction "P87_9") (pintype "passive"))
    )
    (net (code "113") (name "unconnected-(U6-P88-Pad24)") (class "Default")
      (node (ref "U6") (pin "24") (pinfunction "P88_24") (pintype "passive"))
    )
    (net (code "114") (name "unconnected-(U6-PWM-Pad10)") (class "Default")
      (node (ref "U6") (pin "10") (pinfunction "PWM_10") (pintype "passive"))
    )
    (net (code "115") (name "unconnected-(U6-RX2-Pad32)") (class "Default")
      (node (ref "U6") (pin "32") (pinfunction "RX2_32") (pintype "passive"))
    )
    (net (code "116") (name "unconnected-(U6-SCL1-Pad35)") (class "Default")
      (node (ref "U6") (pin "35") (pinfunction "SCL1_35") (pintype "passive"))
    )
    (net (code "117") (name "unconnected-(U6-SDA1-Pad37)") (class "Default")
      (node (ref "U6") (pin "37") (pinfunction "SDA1_37") (pintype "passive"))
    )
    (net (code "118") (name "unconnected-(U6-TX2-Pad34)") (class "Default")
      (node (ref "U6") (pin "34") (pinfunction "TX2_34") (pintype "passive"))
    )
    (net (code "119") (name "unconnected-(USB-D+-Pad3)") (class "Default")
      (node (ref "USB") (pin "3") (pinfunction "D+_3") (pintype "passive+no_connect"))
    )
    (net (code "120") (name "unconnected-(USB-D--Pad2)") (class "Default")
      (node (ref "USB") (pin "2") (pinfunction "D-_2") (pintype "passive+no_connect"))
    )
    (net (code "121") (name "unconnected-(USB-ID-Pad4)") (class "Default")
      (node (ref "USB") (pin "4") (pinfunction "ID_4") (pintype "passive+no_connect"))
    )
  )
)
